# UBC-Thunderbots_PCB_Power__power-v3_1_pc.net
KiCad netlist of a schematic drawn in Altium Designer
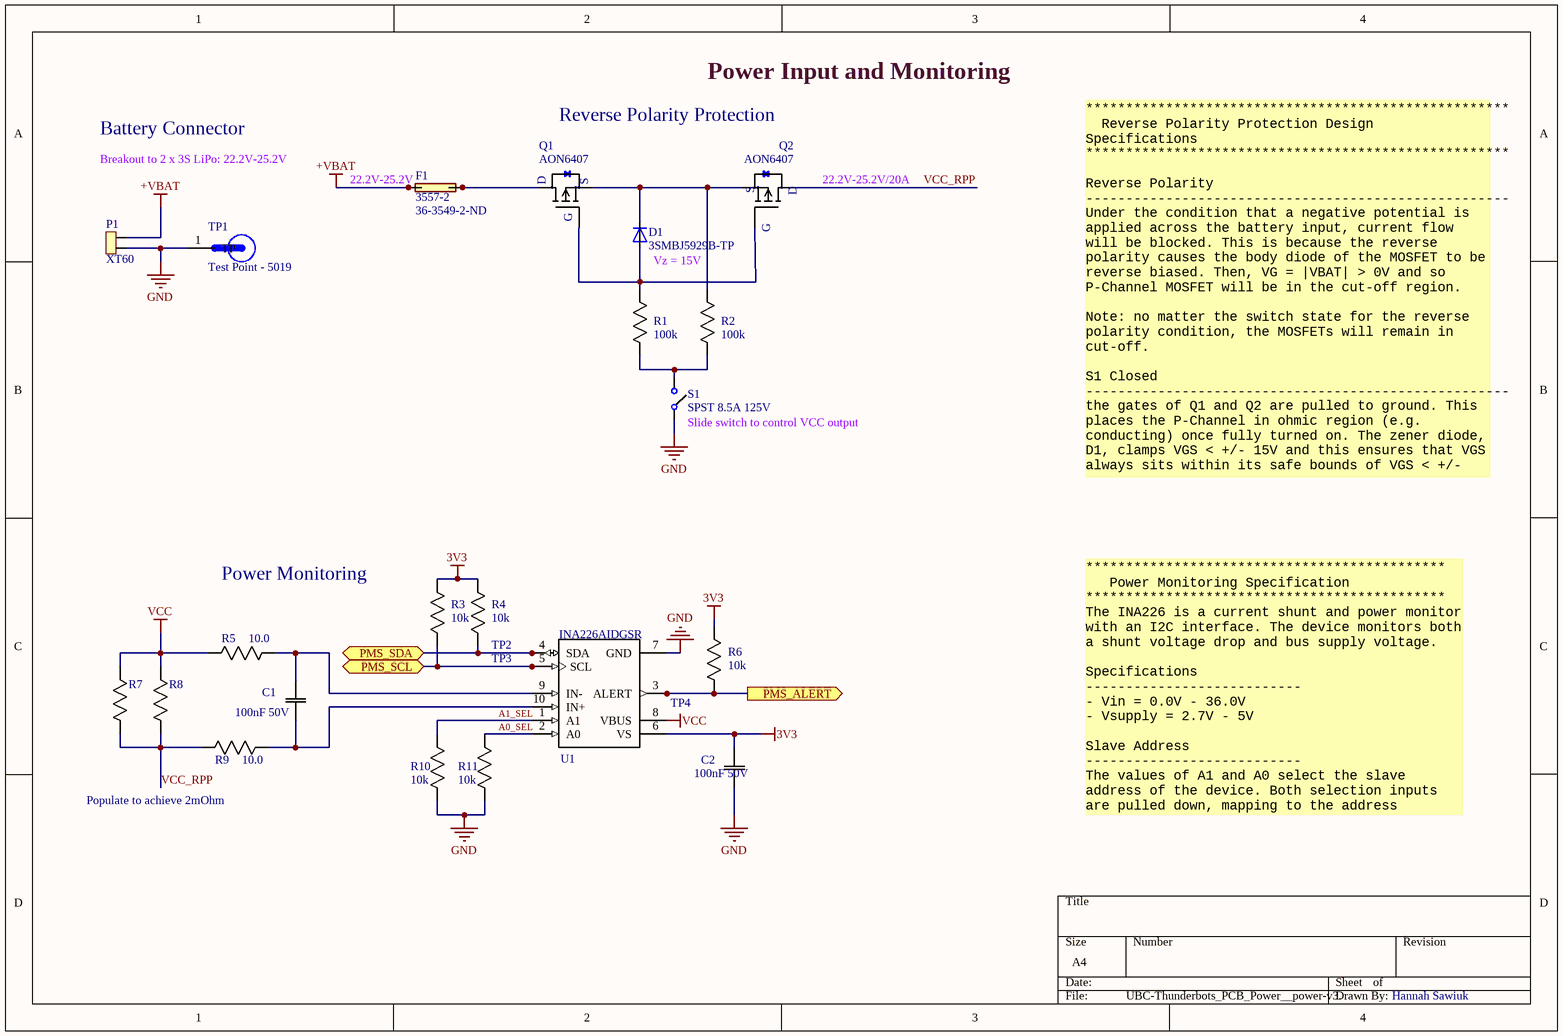
[diagram p0: UBC-Thunderbots_PCB_Power__power-v3.1_pcb__power-input.SchDoc]

(export (version "E")
  (design (tool "Eeschema 10.0.6"))
  (components
    (comp (ref "C1")
      (value "100nF 50V")
      (footprint "0805")
      (description "CAP CER 0.1UF 50V X7R 0805")
      (fields (field (name "TOLERANCE") "10%"))
      (libsource (lib "AltiumLibraries") (part "CAP 100nF 50V"))
    )
    (comp (ref "C2")
      (value "100nF 50V")
      (footprint "0805")
      (description "CAP CER 0.1UF 50V X7R 0805")
      (fields (field (name "TOLERANCE") "10%"))
      (libsource (lib "AltiumLibraries") (part "CAP 100nF 50V"))
    )
    (comp (ref "D1")
      (value "3SMBJ5929B-TP")
      (footprint "SOD-123")
      (description "Diode ZENER 15V 3W")
      (libsource (lib "AltiumLibraries") (part "DIODE ZENER 15V 3W"))
    )
    (comp (ref "F1")
      (value "3557-2")
      (footprint "FUSE_3549-2")
      (description "Fuse Block 30A 500V 1 Circuit Blade Through Hole")
      (fields
        (field (name "MF") "Keystone Electronics")
        (field (name "SUPPLIER PART NUMBER 2") "36-3549-2-ND")
      )
      (libsource (lib "AltiumLibraries") (part "FUSE BLADE"))
    )
    (comp (ref "P1")
      (value "XT60")
      (footprint "Amass_XT60PW-M")
      (description "XT60 CONNECTORS FEMALE PAIR")
      (fields (field (name "MF") "SparkFun Electronics") (field (name "MP") "PRT-10474"))
      (libsource (lib "AltiumLibraries") (part "XT60 Connector"))
    )
    (comp (ref "Q1")
      (value "AON6407")
      (footprint "8-PowerSMD")
      (description "MOSFET P-CH 30V 32A 8DFN")
      (fields (field (name "MF") "Alpha & Omega Semiconductor Inc."))
      (libsource (lib "AltiumLibraries") (part "MOSFET AON6407"))
    )
    (comp (ref "Q2")
      (value "AON6407")
      (footprint "8-PowerSMD")
      (description "MOSFET P-CH 30V 32A 8DFN")
      (fields (field (name "MF") "Alpha & Omega Semiconductor Inc."))
      (libsource (lib "AltiumLibraries") (part "MOSFET AON6407"))
    )
    (comp (ref "R1")
      (value "100k")
      (footprint "0805")
      (description "RES SMD 100K OHM 1% 1/8W 0805")
      (fields (field (name "TOLERANCE") "1%"))
      (libsource (lib "AltiumLibraries") (part "RES 100k 1/8W - 1%"))
    )
    (comp (ref "R2")
      (value "100k")
      (footprint "0805")
      (description "RES SMD 100K OHM 1% 1/8W 0805")
      (fields (field (name "TOLERANCE") "1%"))
      (libsource (lib "AltiumLibraries") (part "RES 100k 1/8W - 1%"))
    )
    (comp (ref "R3")
      (value "10k")
      (footprint "0805")
      (description "RES SMD 10K OHM 1% 1/8W 0805")
      (fields (field (name "TOLERANCE") "1%"))
      (libsource (lib "") (part "RES 10k 1/8W - 1%_1"))
    )
    (comp (ref "R4")
      (value "10k")
      (footprint "0805")
      (description "RES SMD 10K OHM 1% 1/8W 0805")
      (fields (field (name "TOLERANCE") "1%"))
      (libsource (lib "") (part "RES 10k 1/8W - 1%_1"))
    )
    (comp (ref "R5")
      (value "10.0")
      (footprint "0805")
      (description "RES SMD 10.0 OHM 1% 1/8W 0805")
      (fields (field (name "TOLERANCE") "1%"))
      (libsource (lib "AltiumLibraries") (part "RES 10.0 1/8W - 1%"))
    )
    (comp (ref "R6")
      (value "10k")
      (footprint "0805")
      (description "RES SMD 10K OHM 1% 1/8W 0805")
      (fields (field (name "TOLERANCE") "1%"))
      (libsource (lib "") (part "RES 10k 1/8W - 1%_1"))
    )
    (comp (ref "R7")
      (value "2mOHM")
      (footprint "2512")
      (description "RES SMD 2m OHM 1% 1W 1206")
      (fields (field (name "TOLERANCE") "1%"))
      (libsource (lib "AltiumLibraries") (part "RES 2m 1W"))
    )
    (comp (ref "R8")
      (value "2mOHM")
      (footprint "2512")
      (description "RES SMD 2m OHM 1% 1W 1206")
      (fields (field (name "TOLERANCE") "1%"))
      (libsource (lib "AltiumLibraries") (part "RES 2m 1W"))
    )
    (comp (ref "R9")
      (value "10.0")
      (footprint "0805")
      (description "RES SMD 10.0 OHM 1% 1/8W 0805")
      (fields (field (name "TOLERANCE") "1%"))
      (libsource (lib "AltiumLibraries") (part "RES 10.0 1/8W - 1%"))
    )
    (comp (ref "R10")
      (value "10k")
      (footprint "0805")
      (description "RES SMD 10K OHM 1% 1/8W 0805")
      (fields (field (name "TOLERANCE") "1%"))
      (libsource (lib "AltiumLibraries") (part "RES 10k 1/8W - 1%"))
    )
    (comp (ref "R11")
      (value "10k")
      (footprint "0805")
      (description "RES SMD 10K OHM 1% 1/8W 0805")
      (fields (field (name "TOLERANCE") "1%"))
      (libsource (lib "AltiumLibraries") (part "RES 10k 1/8W - 1%"))
    )
    (comp (ref "S1")
      (value "SPST 8.5A 125V")
      (footprint "SPST GF-123-0054")
      (description "SWITCH SLIDE SPST 8.5A 125V")
      (fields (field (name "MP") "GF-123-0054") (field (name "MF") "CW Industries"))
      (libsource (lib "AltiumLibraries") (part "SW SLIDE"))
    )
    (comp (ref "TP1")
      (value "Test Point - 5019")
      (footprint "TP380X203")
      (description "PC Test Point, Miniature Phosphor Bronze, Silver Plating Surface Mount Mounting Type")
      (fields (field (name "MP") "5019") (field (name "MF") "Keystone Electronics"))
      (libsource (lib "AltiumLibraries") (part "Test Point - 5019"))
    )
    (comp (ref "TP2")
      (value "Test Point (Via)")
      (footprint "TP")
      (libsource (lib "AltiumLibraries") (part "Test Point (Via)"))
    )
    (comp (ref "TP3")
      (value "Test Point (Via)")
      (footprint "TP")
      (libsource (lib "AltiumLibraries") (part "Test Point (Via)"))
    )
    (comp (ref "TP4")
      (value "Test Point (Via)")
      (footprint "TP")
      (libsource (lib "AltiumLibraries") (part "Test Point (Via)"))
    )
    (comp (ref "U1")
      (value "INA226AIDGSR")
      (footprint "10-VSSOP")
      (fields (field (name "MF") "Texas Instruments"))
      (libsource (lib "AltiumLibraries") (part "IC INA226AIDGSR"))
    )
  )
  (nets
    (net (code "1") (name "+VBAT") (class "Default")
      (node (ref "F1") (pin "3") (pinfunction "2A_3") (pintype "passive"))
      (node (ref "F1") (pin "4") (pinfunction "2B_4") (pintype "passive"))
      (node (ref "P1") (pin "2") (pinfunction "2_2") (pintype "passive"))
    )
    (net (code "2") (name "/A0_SEL") (class "Default")
      (node (ref "R11") (pin "1") (pinfunction "R1_1") (pintype "passive"))
      (node (ref "U1") (pin "2") (pinfunction "A0_2") (pintype "input"))
    )
    (net (code "3") (name "/A1_SEL") (class "Default")
      (node (ref "R10") (pin "1") (pinfunction "R1_1") (pintype "passive"))
      (node (ref "U1") (pin "1") (pinfunction "A1_1") (pintype "input"))
    )
    (net (code "4") (name "/PMS_ALERT") (class "Default")
      (node (ref "R6") (pin "2") (pinfunction "R2_2") (pintype "passive"))
      (node (ref "TP4") (pin "1") (pinfunction "1_1") (pintype "passive"))
      (node (ref "U1") (pin "3") (pinfunction "ALERT_3") (pintype "output"))
    )
    (net (code "5") (name "/PMS_SCL") (class "Default")
      (node (ref "R3") (pin "2") (pinfunction "R2_2") (pintype "passive"))
      (node (ref "TP3") (pin "1") (pinfunction "1_1") (pintype "passive"))
      (node (ref "U1") (pin "5") (pinfunction "SCL_5") (pintype "input"))
    )
    (net (code "6") (name "/PMS_SDA") (class "Default")
      (node (ref "R4") (pin "2") (pinfunction "R2_2") (pintype "passive"))
      (node (ref "TP2") (pin "1") (pinfunction "1_1") (pintype "passive"))
      (node (ref "U1") (pin "4") (pinfunction "SDA_4") (pintype "bidirectional"))
    )
    (net (code "7") (name "/VCC_RPP") (class "Default")
      (node (ref "Q2") (pin "D") (pinfunction "D_D") (pintype "passive"))
      (node (ref "R7") (pin "2") (pinfunction "R2_2") (pintype "passive"))
      (node (ref "R8") (pin "2") (pinfunction "R2_2") (pintype "passive"))
      (node (ref "R9") (pin "2") (pinfunction "R2_2") (pintype "passive"))
    )
    (net (code "8") (name "3V3") (class "Default")
      (node (ref "C2") (pin "2") (pinfunction "C2_2") (pintype "passive"))
      (node (ref "R3") (pin "1") (pinfunction "R1_1") (pintype "passive"))
      (node (ref "R4") (pin "1") (pinfunction "R1_1") (pintype "passive"))
      (node (ref "R6") (pin "1") (pinfunction "R1_1") (pintype "passive"))
      (node (ref "U1") (pin "6") (pinfunction "VS_6") (pintype "power_in"))
    )
    (net (code "9") (name "GND") (class "Default")
      (node (ref "C2") (pin "1") (pinfunction "C1_1") (pintype "passive"))
      (node (ref "P1") (pin "1") (pinfunction "1_1") (pintype "passive"))
      (node (ref "R10") (pin "2") (pinfunction "R2_2") (pintype "passive"))
      (node (ref "R11") (pin "2") (pinfunction "R2_2") (pintype "passive"))
      (node (ref "S1") (pin "0") (pinfunction "0_0") (pintype "passive"))
      (node (ref "TP1") (pin "1") (pinfunction "TP_1") (pintype "passive"))
      (node (ref "U1") (pin "7") (pinfunction "GND_7") (pintype "power_in"))
    )
    (net (code "10") (name "Net-(C1-C1)") (class "Default")
      (node (ref "C1") (pin "1") (pinfunction "C1_1") (pintype "passive"))
      (node (ref "R9") (pin "1") (pinfunction "R1_1") (pintype "passive"))
      (node (ref "U1") (pin "10") (pinfunction "IN+_10") (pintype "input"))
    )
    (net (code "11") (name "Net-(C1-C2)") (class "Default")
      (node (ref "C1") (pin "2") (pinfunction "C2_2") (pintype "passive"))
      (node (ref "R5") (pin "1") (pinfunction "R1_1") (pintype "passive"))
      (node (ref "U1") (pin "9") (pinfunction "IN-_9") (pintype "input"))
    )
    (net (code "12") (name "Net-(F1-1A)") (class "Default")
      (node (ref "F1") (pin "1") (pinfunction "1A_1") (pintype "passive"))
      (node (ref "F1") (pin "2") (pinfunction "1B_2") (pintype "passive"))
      (node (ref "Q1") (pin "D") (pinfunction "D_D") (pintype "passive"))
    )
    (net (code "13") (name "Net-(R1-R1)") (class "Default")
      (node (ref "D1") (pin "A") (pinfunction "A_A") (pintype "passive"))
      (node (ref "Q1") (pin "G") (pinfunction "G_G") (pintype "passive"))
      (node (ref "Q2") (pin "G") (pinfunction "G_G") (pintype "passive"))
      (node (ref "R1") (pin "1") (pinfunction "R1_1") (pintype "passive"))
    )
    (net (code "14") (name "Net-(R1-R2)") (class "Default")
      (node (ref "R1") (pin "2") (pinfunction "R2_2") (pintype "passive"))
      (node (ref "R2") (pin "2") (pinfunction "R2_2") (pintype "passive"))
      (node (ref "S1") (pin "1") (pinfunction "1_1") (pintype "passive"))
    )
    (net (code "15") (name "Net-(R2-R1)") (class "Default")
      (node (ref "D1") (pin "C") (pinfunction "C_C") (pintype "passive"))
      (node (ref "Q1") (pin "S") (pinfunction "S_S") (pintype "passive"))
      (node (ref "Q2") (pin "S") (pinfunction "S_S") (pintype "passive"))
      (node (ref "R2") (pin "1") (pinfunction "R1_1") (pintype "passive"))
    )
    (net (code "16") (name "VCC") (class "Default")
      (node (ref "R5") (pin "2") (pinfunction "R2_2") (pintype "passive"))
      (node (ref "R7") (pin "1") (pinfunction "R1_1") (pintype "passive"))
      (node (ref "R8") (pin "1") (pinfunction "R1_1") (pintype "passive"))
      (node (ref "U1") (pin "8") (pinfunction "VBUS_8") (pintype "power_in"))
    )
  )
)
